# PIC.net
KiCad netlist of a schematic drawn in Altium Designer
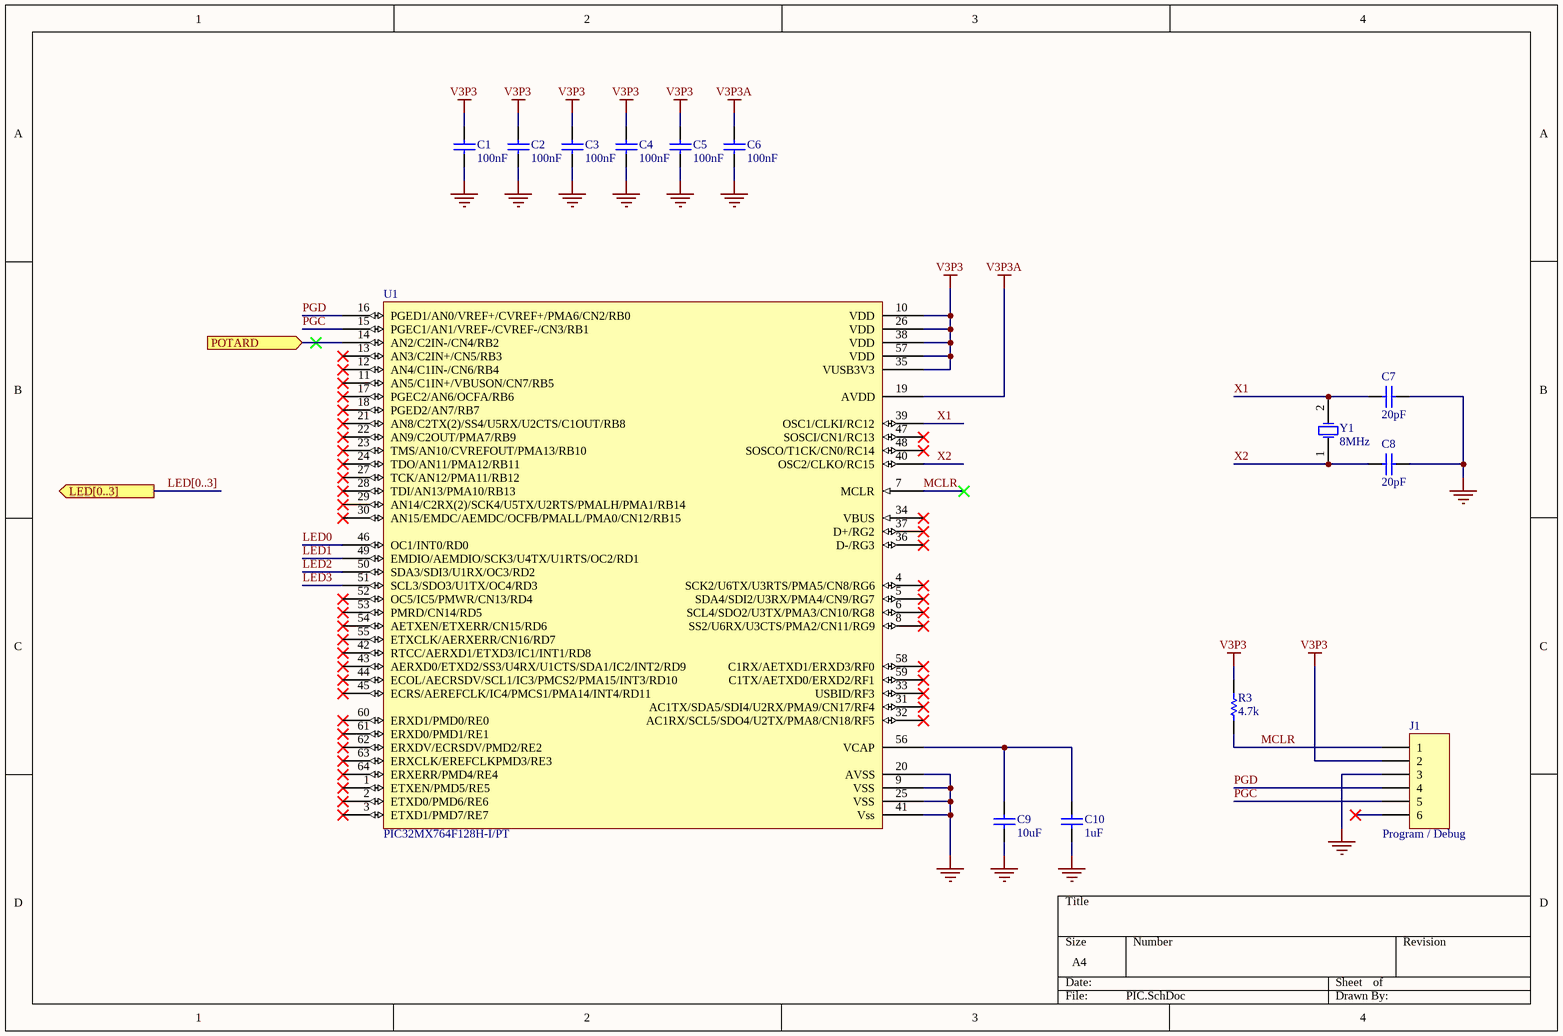
[diagram p0: PIC.SchDoc]

(export (version "E")
  (design (tool "Eeschema 10.0.6"))
  (components
    (comp (ref "C1")
      (value "100nF")
      (footprint "2012/0805")
      (description "Capacitor")
      (fields (field (name "PUBLISHER") "Altium Limited"))
      (libsource (lib "TP3_lib") (part "Capacitor"))
    )
    (comp (ref "C2")
      (value "100nF")
      (footprint "2012/0805")
      (description "Capacitor")
      (fields (field (name "PUBLISHER") "Altium Limited"))
      (libsource (lib "TP3_lib") (part "Capacitor"))
    )
    (comp (ref "C3")
      (value "100nF")
      (footprint "2012/0805")
      (description "Capacitor")
      (fields (field (name "PUBLISHER") "Altium Limited"))
      (libsource (lib "TP3_lib") (part "Capacitor"))
    )
    (comp (ref "C4")
      (value "100nF")
      (footprint "2012/0805")
      (description "Capacitor")
      (fields (field (name "PUBLISHER") "Altium Limited"))
      (libsource (lib "TP3_lib") (part "Capacitor"))
    )
    (comp (ref "C5")
      (value "100nF")
      (footprint "2012/0805")
      (description "Capacitor")
      (fields (field (name "PUBLISHER") "Altium Limited"))
      (libsource (lib "TP3_lib") (part "Capacitor"))
    )
    (comp (ref "C6")
      (value "100nF")
      (footprint "2012/0805")
      (description "Capacitor")
      (fields (field (name "PUBLISHER") "Altium Limited"))
      (libsource (lib "TP3_lib") (part "Capacitor"))
    )
    (comp (ref "C7")
      (value "20pF")
      (footprint "2012/0805")
      (description "Capacitor")
      (fields (field (name "PUBLISHER") "Altium Limited"))
      (libsource (lib "TP3_lib") (part "Capacitor"))
    )
    (comp (ref "C8")
      (value "20pF")
      (footprint "2012/0805")
      (description "Capacitor")
      (fields (field (name "PUBLISHER") "Altium Limited"))
      (libsource (lib "TP3_lib") (part "Capacitor"))
    )
    (comp (ref "C9")
      (value "10uF")
      (footprint "2012/0805")
      (description "Capacitor")
      (fields (field (name "PUBLISHER") "Altium Limited"))
      (libsource (lib "TP3_lib") (part "Capacitor"))
    )
    (comp (ref "C10")
      (value "1uF")
      (footprint "2012/0805")
      (description "Capacitor")
      (fields (field (name "PUBLISHER") "Altium Limited"))
      (libsource (lib "TP3_lib") (part "Capacitor"))
    )
    (comp (ref "J1")
      (value "Program / Debug")
      (footprint "TD03B_N")
      (description "Header, 6-Pin")
      (fields (field (name "PUBLISHER") "Altium Limited"))
      (libsource (lib "TP3_lib") (part "Header 6"))
    )
    (comp (ref "R3")
      (value "4.7k")
      (footprint "1608/0603")
      (description "Resistor")
      (fields (field (name "PUBLISHER") "Altium Limited"))
      (libsource (lib "TP3_lib") (part "Resistor"))
    )
    (comp (ref "U1")
      (value "PIC32MX764F128H-I/PT")
      (footprint "PIC32MX")
      (libsource (lib "TP3_lib") (part "PIC"))
    )
    (comp (ref "Y1")
      (value "8MHz")
      (footprint "XTAL139X50X45")
      (description "Crystal Oscillator")
      (fields (field (name "PUBLISHER") "Altium Limited"))
      (libsource (lib "TP3_lib") (part "Crystal"))
    )
  )
  (nets
    (net (code "1") (name "/LED0") (class "Default")
      (node (ref "U1") (pin "46") (pinfunction "OC1/INT0/RD0_46") (pintype "bidirectional"))
    )
    (net (code "2") (name "/LED1") (class "Default")
      (node (ref "U1") (pin "49") (pinfunction "EMDIO/AEMDIO/SCK3/U4TX/U1RTS/OC2/RD1_49") (pintype "bidirectional"))
    )
    (net (code "3") (name "/LED2") (class "Default")
      (node (ref "U1") (pin "50") (pinfunction "SDA3/SDI3/U1RX/OC3/RD2_50") (pintype "bidirectional"))
    )
    (net (code "4") (name "/LED3") (class "Default")
      (node (ref "U1") (pin "51") (pinfunction "SCL3/SDO3/U1TX/OC4/RD3_51") (pintype "bidirectional"))
    )
    (net (code "6") (name "/MCLR") (class "Default")
      (node (ref "J1") (pin "1") (pinfunction "1_1") (pintype "passive"))
      (node (ref "R3") (pin "1") (pinfunction "1_1") (pintype "passive"))
      (node (ref "U1") (pin "7") (pinfunction "MCLR_7") (pintype "input"))
    )
    (net (code "7") (name "/PGC") (class "Default")
      (node (ref "J1") (pin "5") (pinfunction "5_5") (pintype "passive"))
      (node (ref "U1") (pin "15") (pinfunction "PGEC1/AN1/VREF-/CVREF-/CN3/RB1_15") (pintype "bidirectional"))
    )
    (net (code "8") (name "/PGD") (class "Default")
      (node (ref "J1") (pin "4") (pinfunction "4_4") (pintype "passive"))
      (node (ref "U1") (pin "16") (pinfunction "PGED1/AN0/VREF+/CVREF+/PMA6/CN2/RB0_16") (pintype "bidirectional"))
    )
    (net (code "9") (name "/POTARD") (class "Default")
      (node (ref "U1") (pin "14") (pinfunction "AN2/C2IN-/CN4/RB2_14") (pintype "bidirectional+no_connect"))
    )
    (net (code "10") (name "/X1") (class "Default")
      (node (ref "C7") (pin "1") (pinfunction "1_1") (pintype "passive"))
      (node (ref "U1") (pin "39") (pinfunction "OSC1/CLKI/RC12_39") (pintype "bidirectional"))
      (node (ref "Y1") (pin "2") (pinfunction "OSC2_2") (pintype "passive"))
    )
    (net (code "11") (name "/X2") (class "Default")
      (node (ref "C8") (pin "1") (pinfunction "1_1") (pintype "passive"))
      (node (ref "U1") (pin "40") (pinfunction "OSC2/CLKO/RC15_40") (pintype "bidirectional"))
      (node (ref "Y1") (pin "1") (pinfunction "OSC1_1") (pintype "passive"))
    )
    (net (code "12") (name "GND") (class "Default")
      (node (ref "C1") (pin "1") (pinfunction "1_1") (pintype "passive"))
      (node (ref "C10") (pin "1") (pinfunction "1_1") (pintype "passive"))
      (node (ref "C2") (pin "1") (pinfunction "1_1") (pintype "passive"))
      (node (ref "C3") (pin "1") (pinfunction "1_1") (pintype "passive"))
      (node (ref "C4") (pin "1") (pinfunction "1_1") (pintype "passive"))
      (node (ref "C5") (pin "1") (pinfunction "1_1") (pintype "passive"))
      (node (ref "C6") (pin "1") (pinfunction "1_1") (pintype "passive"))
      (node (ref "C7") (pin "2") (pinfunction "2_2") (pintype "passive"))
      (node (ref "C8") (pin "2") (pinfunction "2_2") (pintype "passive"))
      (node (ref "C9") (pin "1") (pinfunction "1_1") (pintype "passive"))
      (node (ref "J1") (pin "3") (pinfunction "3_3") (pintype "passive"))
      (node (ref "U1") (pin "20") (pinfunction "AVSS_20") (pintype "power_in"))
      (node (ref "U1") (pin "25") (pinfunction "VSS_25") (pintype "power_in"))
      (node (ref "U1") (pin "41") (pinfunction "Vss_41") (pintype "power_in"))
      (node (ref "U1") (pin "9") (pinfunction "VSS_9") (pintype "power_in"))
    )
    (net (code "13") (name "Net-(U1-VCAP)") (class "Default")
      (node (ref "C10") (pin "2") (pinfunction "2_2") (pintype "passive"))
      (node (ref "C9") (pin "2") (pinfunction "2_2") (pintype "passive"))
      (node (ref "U1") (pin "56") (pinfunction "VCAP_56") (pintype "power_in"))
    )
    (net (code "14") (name "V3P3") (class "Default")
      (node (ref "C1") (pin "2") (pinfunction "2_2") (pintype "passive"))
      (node (ref "C2") (pin "2") (pinfunction "2_2") (pintype "passive"))
      (node (ref "C3") (pin "2") (pinfunction "2_2") (pintype "passive"))
      (node (ref "C4") (pin "2") (pinfunction "2_2") (pintype "passive"))
      (node (ref "C5") (pin "2") (pinfunction "2_2") (pintype "passive"))
      (node (ref "J1") (pin "2") (pinfunction "2_2") (pintype "passive"))
      (node (ref "R3") (pin "2") (pinfunction "2_2") (pintype "passive"))
      (node (ref "U1") (pin "10") (pinfunction "VDD_10") (pintype "power_in"))
      (node (ref "U1") (pin "26") (pinfunction "VDD_26") (pintype "power_in"))
      (node (ref "U1") (pin "35") (pinfunction "VUSB3V3_35") (pintype "power_in"))
      (node (ref "U1") (pin "38") (pinfunction "VDD_38") (pintype "power_in"))
      (node (ref "U1") (pin "57") (pinfunction "VDD_57") (pintype "power_in"))
    )
    (net (code "15") (name "V3P3A") (class "Default")
      (node (ref "C6") (pin "2") (pinfunction "2_2") (pintype "passive"))
      (node (ref "U1") (pin "19") (pinfunction "AVDD_19") (pintype "power_in"))
    )
    (net (code "16") (name "unconnected-(J1-Pad6)") (class "Default")
      (node (ref "J1") (pin "6") (pinfunction "6_6") (pintype "passive+no_connect"))
    )
    (net (code "17") (name "unconnected-(U1-AC1RX{slash}SCL5{slash}SDO4{slash}U2TX{slash}PMA8{slash}CN18{slash}RF5-Pad32)") (class "Default")
      (node (ref "U1") (pin "32") (pinfunction "AC1RX/SCL5/SDO4/U2TX/PMA8/CN18/RF5_32") (pintype "bidirectional+no_connect"))
    )
    (net (code "18") (name "unconnected-(U1-AC1TX{slash}SDA5{slash}SDI4{slash}U2RX{slash}PMA9{slash}CN17{slash}RF4-Pad31)") (class "Default")
      (node (ref "U1") (pin "31") (pinfunction "AC1TX/SDA5/SDI4/U2RX/PMA9/CN17/RF4_31") (pintype "bidirectional+no_connect"))
    )
    (net (code "19") (name "unconnected-(U1-AERXD0{slash}ETXD2{slash}SS3{slash}U4RX{slash}U1CTS{slash}SDA1{slash}IC2{slash}INT2{slash}RD9-Pad43)") (class "Default")
      (node (ref "U1") (pin "43") (pinfunction "AERXD0/ETXD2/SS3/U4RX/U1CTS/SDA1/IC2/INT2/RD9_43") (pintype "bidirectional+no_connect"))
    )
    (net (code "20") (name "unconnected-(U1-AETXEN{slash}ETXERR{slash}CN15{slash}RD6-Pad54)") (class "Default")
      (node (ref "U1") (pin "54") (pinfunction "AETXEN/ETXERR/CN15/RD6_54") (pintype "bidirectional+no_connect"))
    )
    (net (code "21") (name "unconnected-(U1-AN3{slash}C2IN+{slash}CN5{slash}RB3-Pad13)") (class "Default")
      (node (ref "U1") (pin "13") (pinfunction "AN3/C2IN+/CN5/RB3_13") (pintype "bidirectional+no_connect"))
    )
    (net (code "22") (name "unconnected-(U1-AN4{slash}C1IN-{slash}CN6{slash}RB4-Pad12)") (class "Default")
      (node (ref "U1") (pin "12") (pinfunction "AN4/C1IN-/CN6/RB4_12") (pintype "bidirectional+no_connect"))
    )
    (net (code "23") (name "unconnected-(U1-AN5{slash}C1IN+{slash}VBUSON{slash}CN7{slash}RB5-Pad11)") (class "Default")
      (node (ref "U1") (pin "11") (pinfunction "AN5/C1IN+/VBUSON/CN7/RB5_11") (pintype "bidirectional+no_connect"))
    )
    (net (code "24") (name "unconnected-(U1-AN8{slash}C2TX(2){slash}SS4{slash}U5RX{slash}U2CTS{slash}C1OUT{slash}RB8-Pad21)") (class "Default")
      (node (ref "U1") (pin "21") (pinfunction "AN8/C2TX(2)/SS4/U5RX/U2CTS/C1OUT/RB8_21") (pintype "bidirectional+no_connect"))
    )
    (net (code "25") (name "unconnected-(U1-AN9{slash}C2OUT{slash}PMA7{slash}RB9-Pad22)") (class "Default")
      (node (ref "U1") (pin "22") (pinfunction "AN9/C2OUT/PMA7/RB9_22") (pintype "bidirectional+no_connect"))
    )
    (net (code "26") (name "unconnected-(U1-AN14{slash}C2RX(2){slash}SCK4{slash}U5TX{slash}U2RTS{slash}PMALH{slash}PMA1{slash}RB14-Pad29)") (class "Default")
      (node (ref "U1") (pin "29") (pinfunction "AN14/C2RX(2)/SCK4/U5TX/U2RTS/PMALH/PMA1/RB14_29") (pintype "bidirectional+no_connect"))
    )
    (net (code "27") (name "unconnected-(U1-AN15{slash}EMDC{slash}AEMDC{slash}OCFB{slash}PMALL{slash}PMA0{slash}CN12{slash}RB15-Pad30)") (class "Default")
      (node (ref "U1") (pin "30") (pinfunction "AN15/EMDC/AEMDC/OCFB/PMALL/PMA0/CN12/RB15_30") (pintype "bidirectional+no_connect"))
    )
    (net (code "28") (name "unconnected-(U1-C1RX{slash}AETXD1{slash}ERXD3{slash}RF0-Pad58)") (class "Default")
      (node (ref "U1") (pin "58") (pinfunction "C1RX/AETXD1/ERXD3/RF0_58") (pintype "bidirectional+no_connect"))
    )
    (net (code "29") (name "unconnected-(U1-C1TX{slash}AETXD0{slash}ERXD2{slash}RF1-Pad59)") (class "Default")
      (node (ref "U1") (pin "59") (pinfunction "C1TX/AETXD0/ERXD2/RF1_59") (pintype "bidirectional+no_connect"))
    )
    (net (code "30") (name "unconnected-(U1-D+{slash}RG2-Pad37)") (class "Default")
      (node (ref "U1") (pin "37") (pinfunction "D+/RG2_37") (pintype "bidirectional+no_connect"))
    )
    (net (code "31") (name "unconnected-(U1-D-{slash}RG3-Pad36)") (class "Default")
      (node (ref "U1") (pin "36") (pinfunction "D-/RG3_36") (pintype "bidirectional+no_connect"))
    )
    (net (code "32") (name "unconnected-(U1-ECOL{slash}AECRSDV{slash}SCL1{slash}IC3{slash}PMCS2{slash}PMA15{slash}INT3{slash}RD10-Pad44)") (class "Default")
      (node (ref "U1") (pin "44") (pinfunction "ECOL/AECRSDV/SCL1/IC3/PMCS2/PMA15/INT3/RD10_44") (pintype "bidirectional+no_connect"))
    )
    (net (code "33") (name "unconnected-(U1-ECRS{slash}AEREFCLK{slash}IC4{slash}PMCS1{slash}PMA14{slash}INT4{slash}RD11-Pad45)") (class "Default")
      (node (ref "U1") (pin "45") (pinfunction "ECRS/AEREFCLK/IC4/PMCS1/PMA14/INT4/RD11_45") (pintype "bidirectional+no_connect"))
    )
    (net (code "34") (name "unconnected-(U1-ERXCLK{slash}EREFCLKPMD3{slash}RE3-Pad63)") (class "Default")
      (node (ref "U1") (pin "63") (pinfunction "ERXCLK/EREFCLKPMD3/RE3_63") (pintype "bidirectional+no_connect"))
    )
    (net (code "35") (name "unconnected-(U1-ERXD0{slash}PMD1{slash}RE1-Pad61)") (class "Default")
      (node (ref "U1") (pin "61") (pinfunction "ERXD0/PMD1/RE1_61") (pintype "bidirectional+no_connect"))
    )
    (net (code "36") (name "unconnected-(U1-ERXD1{slash}PMD0{slash}RE0-Pad60)") (class "Default")
      (node (ref "U1") (pin "60") (pinfunction "ERXD1/PMD0/RE0_60") (pintype "bidirectional+no_connect"))
    )
    (net (code "37") (name "unconnected-(U1-ERXDV{slash}ECRSDV{slash}PMD2{slash}RE2-Pad62)") (class "Default")
      (node (ref "U1") (pin "62") (pinfunction "ERXDV/ECRSDV/PMD2/RE2_62") (pintype "bidirectional+no_connect"))
    )
    (net (code "38") (name "unconnected-(U1-ERXERR{slash}PMD4{slash}RE4-Pad64)") (class "Default")
      (node (ref "U1") (pin "64") (pinfunction "ERXERR/PMD4/RE4_64") (pintype "bidirectional+no_connect"))
    )
    (net (code "39") (name "unconnected-(U1-ETXCLK{slash}AERXERR{slash}CN16{slash}RD7-Pad55)") (class "Default")
      (node (ref "U1") (pin "55") (pinfunction "ETXCLK/AERXERR/CN16/RD7_55") (pintype "bidirectional+no_connect"))
    )
    (net (code "40") (name "unconnected-(U1-ETXD0{slash}PMD6{slash}RE6-Pad2)") (class "Default")
      (node (ref "U1") (pin "2") (pinfunction "ETXD0/PMD6/RE6_2") (pintype "bidirectional+no_connect"))
    )
    (net (code "41") (name "unconnected-(U1-ETXD1{slash}PMD7{slash}RE7-Pad3)") (class "Default")
      (node (ref "U1") (pin "3") (pinfunction "ETXD1/PMD7/RE7_3") (pintype "bidirectional+no_connect"))
    )
    (net (code "42") (name "unconnected-(U1-ETXEN{slash}PMD5{slash}RE5-Pad1)") (class "Default")
      (node (ref "U1") (pin "1") (pinfunction "ETXEN/PMD5/RE5_1") (pintype "bidirectional+no_connect"))
    )
    (net (code "43") (name "unconnected-(U1-OC5{slash}IC5{slash}PMWR{slash}CN13{slash}RD4-Pad52)") (class "Default")
      (node (ref "U1") (pin "52") (pinfunction "OC5/IC5/PMWR/CN13/RD4_52") (pintype "bidirectional+no_connect"))
    )
    (net (code "44") (name "unconnected-(U1-PGEC2{slash}AN6{slash}OCFA{slash}RB6-Pad17)") (class "Default")
      (node (ref "U1") (pin "17") (pinfunction "PGEC2/AN6/OCFA/RB6_17") (pintype "bidirectional+no_connect"))
    )
    (net (code "45") (name "unconnected-(U1-PGED2{slash}AN7{slash}RB7-Pad18)") (class "Default")
      (node (ref "U1") (pin "18") (pinfunction "PGED2/AN7/RB7_18") (pintype "bidirectional+no_connect"))
    )
    (net (code "46") (name "unconnected-(U1-PMRD{slash}CN14{slash}RD5-Pad53)") (class "Default")
      (node (ref "U1") (pin "53") (pinfunction "PMRD/CN14/RD5_53") (pintype "bidirectional+no_connect"))
    )
    (net (code "47") (name "unconnected-(U1-RTCC{slash}AERXD1{slash}ETXD3{slash}IC1{slash}INT1{slash}RD8-Pad42)") (class "Default")
      (node (ref "U1") (pin "42") (pinfunction "RTCC/AERXD1/ETXD3/IC1/INT1/RD8_42") (pintype "bidirectional+no_connect"))
    )
    (net (code "48") (name "unconnected-(U1-SCK2{slash}U6TX{slash}U3RTS{slash}PMA5{slash}CN8{slash}RG6-Pad4)") (class "Default")
      (node (ref "U1") (pin "4") (pinfunction "SCK2/U6TX/U3RTS/PMA5/CN8/RG6_4") (pintype "bidirectional+no_connect"))
    )
    (net (code "49") (name "unconnected-(U1-SCL4{slash}SDO2{slash}U3TX{slash}PMA3{slash}CN10{slash}RG8-Pad6)") (class "Default")
      (node (ref "U1") (pin "6") (pinfunction "SCL4/SDO2/U3TX/PMA3/CN10/RG8_6") (pintype "bidirectional+no_connect"))
    )
    (net (code "50") (name "unconnected-(U1-SDA4{slash}SDI2{slash}U3RX{slash}PMA4{slash}CN9{slash}RG7-Pad5)") (class "Default")
      (node (ref "U1") (pin "5") (pinfunction "SDA4/SDI2/U3RX/PMA4/CN9/RG7_5") (pintype "bidirectional+no_connect"))
    )
    (net (code "51") (name "unconnected-(U1-SOSCI{slash}CN1{slash}RC13-Pad47)") (class "Default")
      (node (ref "U1") (pin "47") (pinfunction "SOSCI/CN1/RC13_47") (pintype "bidirectional+no_connect"))
    )
    (net (code "52") (name "unconnected-(U1-SOSCO{slash}T1CK{slash}CN0{slash}RC14-Pad48)") (class "Default")
      (node (ref "U1") (pin "48") (pinfunction "SOSCO/T1CK/CN0/RC14_48") (pintype "bidirectional+no_connect"))
    )
    (net (code "53") (name "unconnected-(U1-SS2{slash}U6RX{slash}U3CTS{slash}PMA2{slash}CN11{slash}RG9-Pad8)") (class "Default")
      (node (ref "U1") (pin "8") (pinfunction "SS2/U6RX/U3CTS/PMA2/CN11/RG9_8") (pintype "bidirectional+no_connect"))
    )
    (net (code "54") (name "unconnected-(U1-TCK{slash}AN12{slash}PMA11{slash}RB12-Pad27)") (class "Default")
      (node (ref "U1") (pin "27") (pinfunction "TCK/AN12/PMA11/RB12_27") (pintype "bidirectional+no_connect"))
    )
    (net (code "55") (name "unconnected-(U1-TDI{slash}AN13{slash}PMA10{slash}RB13-Pad28)") (class "Default")
      (node (ref "U1") (pin "28") (pinfunction "TDI/AN13/PMA10/RB13_28") (pintype "bidirectional+no_connect"))
    )
    (net (code "56") (name "unconnected-(U1-TDO{slash}AN11{slash}PMA12{slash}RB11-Pad24)") (class "Default")
      (node (ref "U1") (pin "24") (pinfunction "TDO/AN11/PMA12/RB11_24") (pintype "bidirectional+no_connect"))
    )
    (net (code "57") (name "unconnected-(U1-TMS{slash}AN10{slash}CVREFOUT{slash}PMA13{slash}RB10-Pad23)") (class "Default")
      (node (ref "U1") (pin "23") (pinfunction "TMS/AN10/CVREFOUT/PMA13/RB10_23") (pintype "bidirectional+no_connect"))
    )
    (net (code "58") (name "unconnected-(U1-USBID{slash}RF3-Pad33)") (class "Default")
      (node (ref "U1") (pin "33") (pinfunction "USBID/RF3_33") (pintype "bidirectional+no_connect"))
    )
    (net (code "59") (name "unconnected-(U1-VBUS-Pad34)") (class "Default")
      (node (ref "U1") (pin "34") (pinfunction "VBUS_34") (pintype "input+no_connect"))
    )
  )
)
